# Sheet1.net
KiCad netlist of a schematic drawn in Altium Designer
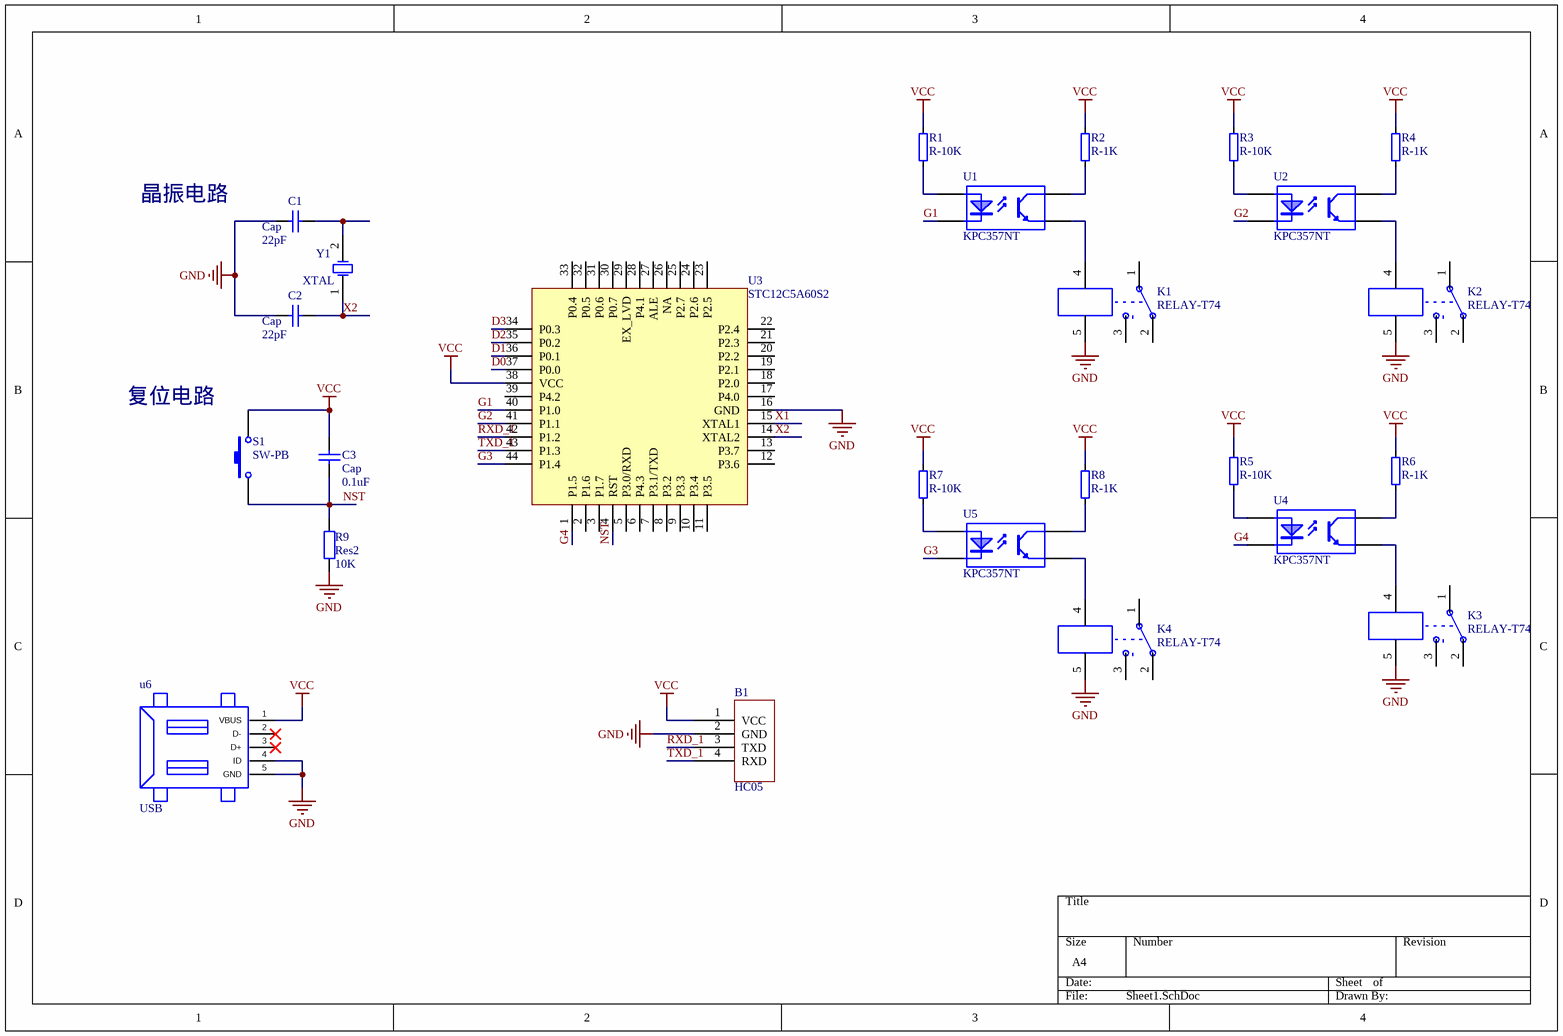
[diagram p0: Sheet1.SchDoc]

(export (version "E")
  (design (tool "Eeschema 10.0.6"))
  (components
    (comp (ref "B1") (value "HC05") (libsource (lib "mine") (part "BT06")))
    (comp (ref "C1")
      (value "Cap")
      (footprint "RAD-0.3")
      (description "Capacitor")
      (fields (field (name "ALTIUM_VALUE") "22pF") (field (name "PUBLISHER") "Altium Limited"))
      (libsource (lib "Miscellaneous Devices") (part "Cap"))
    )
    (comp (ref "C2")
      (value "Cap")
      (footprint "RAD-0.3")
      (description "Capacitor")
      (fields (field (name "ALTIUM_VALUE") "22pF") (field (name "PUBLISHER") "Altium Limited"))
      (libsource (lib "Miscellaneous Devices") (part "Cap"))
    )
    (comp (ref "C3")
      (value "Cap")
      (footprint "RAD-0.3")
      (description "Capacitor")
      (fields (field (name "ALTIUM_VALUE") "0.1uF") (field (name "PUBLISHER") "Altium Limited"))
      (libsource (lib "Miscellaneous Devices") (part "Cap"))
    )
    (comp (ref "K1")
      (value "RELAY-T74")
      (footprint "RELAY-T74")
      (description "CN-RELAY-T74")
      (libsource (lib "常用器件") (part "RELAY-T74"))
    )
    (comp (ref "K2")
      (value "RELAY-T74")
      (footprint "RELAY-T74")
      (description "CN-RELAY-T74")
      (libsource (lib "常用器件") (part "RELAY-T74"))
    )
    (comp (ref "K3")
      (value "RELAY-T74")
      (footprint "RELAY-T74")
      (description "CN-RELAY-T74")
      (libsource (lib "常用器件") (part "RELAY-T74"))
    )
    (comp (ref "K4")
      (value "RELAY-T74")
      (footprint "RELAY-T74")
      (description "CN-RELAY-T74")
      (libsource (lib "常用器件") (part "RELAY-T74"))
    )
    (comp (ref "R1")
      (value "R-10K")
      (footprint "0805R")
      (description "resistor")
      (libsource (lib "常用器件") (part "R-10K"))
    )
    (comp (ref "R2")
      (value "R-1K")
      (footprint "0805R")
      (description "resistor")
      (libsource (lib "常用器件") (part "R-10K"))
    )
    (comp (ref "R3")
      (value "R-10K")
      (footprint "0805R")
      (description "resistor")
      (libsource (lib "常用器件") (part "R-10K"))
    )
    (comp (ref "R4")
      (value "R-1K")
      (footprint "0805R")
      (description "resistor")
      (libsource (lib "常用器件") (part "R-10K"))
    )
    (comp (ref "R5")
      (value "R-10K")
      (footprint "0805R")
      (description "resistor")
      (libsource (lib "常用器件") (part "R-10K"))
    )
    (comp (ref "R6")
      (value "R-1K")
      (footprint "0805R")
      (description "resistor")
      (libsource (lib "常用器件") (part "R-10K"))
    )
    (comp (ref "R7")
      (value "R-10K")
      (footprint "0805R")
      (description "resistor")
      (libsource (lib "常用器件") (part "R-10K"))
    )
    (comp (ref "R8")
      (value "R-1K")
      (footprint "0805R")
      (description "resistor")
      (libsource (lib "常用器件") (part "R-10K"))
    )
    (comp (ref "R9")
      (value "Res2")
      (footprint "AXIAL-0.4")
      (description "Resistor")
      (fields (field (name "ALTIUM_VALUE") "10K") (field (name "PUBLISHER") "Altium Limited"))
      (libsource (lib "Miscellaneous Devices") (part "Res2"))
    )
    (comp (ref "S1")
      (value "SW-PB")
      (footprint "SPST-2")
      (description "Switch")
      (fields (field (name "PUBLISHER") "Altium Limited"))
      (libsource (lib "Miscellaneous Devices") (part "SW-PB"))
    )
    (comp (ref "U1")
      (value "KPC357NT")
      (footprint "DIP-4")
      (fields (field (name "PUBLISHER") "Altium Limited"))
      (libsource (lib "常用器件") (part "KPC357NT"))
    )
    (comp (ref "U2")
      (value "KPC357NT")
      (footprint "DIP-4")
      (fields (field (name "PUBLISHER") "Altium Limited"))
      (libsource (lib "常用器件") (part "KPC357NT"))
    )
    (comp (ref "U3")
      (value "STC12C5A60S2")
      (footprint "TQFP-44")
      (libsource (lib "STC12C5A60") (part "STC12C5A60S2"))
    )
    (comp (ref "U4")
      (value "KPC357NT")
      (footprint "DIP-4")
      (fields (field (name "PUBLISHER") "Altium Limited"))
      (libsource (lib "常用器件") (part "KPC357NT"))
    )
    (comp (ref "U5")
      (value "KPC357NT")
      (footprint "DIP-4")
      (fields (field (name "PUBLISHER") "Altium Limited"))
      (libsource (lib "常用器件") (part "KPC357NT"))
    )
    (comp (ref "u6") (value "USB") (libsource (lib "mine") (part "USB")))
    (comp (ref "Y1")
      (value "XTAL")
      (footprint "R38")
      (description "Crystal Oscillator")
      (fields (field (name "PUBLISHER") "Altium Limited"))
      (libsource (lib "Miscellaneous Devices") (part "XTAL"))
    )
  )
  (nets
    (net (code "1") (name "/D0") (class "Default")
      (node (ref "U3") (pin "37") (pinfunction "P0.0_37") (pintype "passive"))
    )
    (net (code "2") (name "/D1") (class "Default")
      (node (ref "U3") (pin "36") (pinfunction "P0.1_36") (pintype "passive"))
    )
    (net (code "3") (name "/D2") (class "Default")
      (node (ref "U3") (pin "35") (pinfunction "P0.2_35") (pintype "passive"))
    )
    (net (code "4") (name "/D3") (class "Default")
      (node (ref "U3") (pin "34") (pinfunction "P0.3_34") (pintype "passive"))
    )
    (net (code "5") (name "/G1") (class "Default")
      (node (ref "U1") (pin "2") (pinfunction "K_2") (pintype "passive"))
      (node (ref "U3") (pin "40") (pinfunction "P1.0_40") (pintype "passive"))
    )
    (net (code "6") (name "/G2") (class "Default")
      (node (ref "U2") (pin "2") (pinfunction "K_2") (pintype "passive"))
      (node (ref "U3") (pin "41") (pinfunction "P1.1_41") (pintype "passive"))
    )
    (net (code "7") (name "/G3") (class "Default")
      (node (ref "U3") (pin "44") (pinfunction "P1.4_44") (pintype "passive"))
      (node (ref "U5") (pin "2") (pinfunction "K_2") (pintype "passive"))
    )
    (net (code "8") (name "/G4") (class "Default")
      (node (ref "U3") (pin "1") (pinfunction "P1.5_1") (pintype "passive"))
      (node (ref "U4") (pin "2") (pinfunction "K_2") (pintype "passive"))
    )
    (net (code "9") (name "/NST") (class "Default")
      (node (ref "C3") (pin "1") (pinfunction "1_1") (pintype "passive"))
      (node (ref "R9") (pin "2") (pinfunction "2_2") (pintype "passive"))
      (node (ref "S1") (pin "1") (pinfunction "1_1") (pintype "passive"))
      (node (ref "U3") (pin "4") (pinfunction "RST_4") (pintype "passive"))
    )
    (net (code "10") (name "/RXD_1") (class "Default")
      (node (ref "B1") (pin "3") (pinfunction "TXD_3") (pintype "passive"))
      (node (ref "U3") (pin "42") (pinfunction "P1.2_42") (pintype "passive"))
    )
    (net (code "11") (name "/TXD_1") (class "Default")
      (node (ref "B1") (pin "4") (pinfunction "RXD_4") (pintype "passive"))
      (node (ref "U3") (pin "43") (pinfunction "P1.3_43") (pintype "passive"))
    )
    (net (code "12") (name "/X1") (class "Default")
      (node (ref "U3") (pin "15") (pinfunction "XTAL1_15") (pintype "passive"))
    )
    (net (code "13") (name "/X2") (class "Default")
      (node (ref "C2") (pin "2") (pinfunction "2_2") (pintype "passive"))
      (node (ref "U3") (pin "14") (pinfunction "XTAL2_14") (pintype "passive"))
      (node (ref "Y1") (pin "1") (pinfunction "OSC1_1") (pintype "passive"))
    )
    (net (code "14") (name "GND") (class "Default")
      (node (ref "B1") (pin "2") (pinfunction "GND_2") (pintype "passive"))
      (node (ref "C1") (pin "1") (pinfunction "1_1") (pintype "passive"))
      (node (ref "C2") (pin "1") (pinfunction "1_1") (pintype "passive"))
      (node (ref "K1") (pin "5") (pinfunction "5_5") (pintype "passive"))
      (node (ref "K2") (pin "5") (pinfunction "5_5") (pintype "passive"))
      (node (ref "K3") (pin "5") (pinfunction "5_5") (pintype "passive"))
      (node (ref "K4") (pin "5") (pinfunction "5_5") (pintype "passive"))
      (node (ref "R9") (pin "1") (pinfunction "1_1") (pintype "passive"))
      (node (ref "U3") (pin "16") (pinfunction "GND_16") (pintype "power_in"))
      (node (ref "u6") (pin "4") (pinfunction "ID_4") (pintype "passive"))
      (node (ref "u6") (pin "5") (pinfunction "GND_5") (pintype "passive"))
    )
    (net (code "15") (name "Net-(U1-A)") (class "Default")
      (node (ref "R1") (pin "1") (pinfunction "1_1") (pintype "passive"))
      (node (ref "U1") (pin "1") (pinfunction "A_1") (pintype "passive"))
    )
    (net (code "16") (name "Net-(U1-C)") (class "Default")
      (node (ref "R2") (pin "1") (pinfunction "1_1") (pintype "passive"))
      (node (ref "U1") (pin "4") (pinfunction "C_4") (pintype "passive"))
    )
    (net (code "17") (name "Net-(U1-E)") (class "Default")
      (node (ref "K1") (pin "4") (pinfunction "4_4") (pintype "passive"))
      (node (ref "U1") (pin "3") (pinfunction "E_3") (pintype "passive"))
    )
    (net (code "18") (name "Net-(U2-A)") (class "Default")
      (node (ref "R3") (pin "1") (pinfunction "1_1") (pintype "passive"))
      (node (ref "U2") (pin "1") (pinfunction "A_1") (pintype "passive"))
    )
    (net (code "19") (name "Net-(U2-C)") (class "Default")
      (node (ref "R4") (pin "1") (pinfunction "1_1") (pintype "passive"))
      (node (ref "U2") (pin "4") (pinfunction "C_4") (pintype "passive"))
    )
    (net (code "20") (name "Net-(U2-E)") (class "Default")
      (node (ref "K2") (pin "4") (pinfunction "4_4") (pintype "passive"))
      (node (ref "U2") (pin "3") (pinfunction "E_3") (pintype "passive"))
    )
    (net (code "21") (name "Net-(U4-A)") (class "Default")
      (node (ref "R5") (pin "1") (pinfunction "1_1") (pintype "passive"))
      (node (ref "U4") (pin "1") (pinfunction "A_1") (pintype "passive"))
    )
    (net (code "22") (name "Net-(U4-C)") (class "Default")
      (node (ref "R6") (pin "1") (pinfunction "1_1") (pintype "passive"))
      (node (ref "U4") (pin "4") (pinfunction "C_4") (pintype "passive"))
    )
    (net (code "23") (name "Net-(U4-E)") (class "Default")
      (node (ref "K3") (pin "4") (pinfunction "4_4") (pintype "passive"))
      (node (ref "U4") (pin "3") (pinfunction "E_3") (pintype "passive"))
    )
    (net (code "24") (name "Net-(U5-A)") (class "Default")
      (node (ref "R7") (pin "1") (pinfunction "1_1") (pintype "passive"))
      (node (ref "U5") (pin "1") (pinfunction "A_1") (pintype "passive"))
    )
    (net (code "25") (name "Net-(U5-C)") (class "Default")
      (node (ref "R8") (pin "1") (pinfunction "1_1") (pintype "passive"))
      (node (ref "U5") (pin "4") (pinfunction "C_4") (pintype "passive"))
    )
    (net (code "26") (name "Net-(U5-E)") (class "Default")
      (node (ref "K4") (pin "4") (pinfunction "4_4") (pintype "passive"))
      (node (ref "U5") (pin "3") (pinfunction "E_3") (pintype "passive"))
    )
    (net (code "27") (name "Net-(Y1-OSC2)") (class "Default")
      (node (ref "C1") (pin "2") (pinfunction "2_2") (pintype "passive"))
      (node (ref "Y1") (pin "2") (pinfunction "OSC2_2") (pintype "passive"))
    )
    (net (code "28") (name "VCC") (class "Default")
      (node (ref "B1") (pin "1") (pinfunction "VCC_1") (pintype "passive"))
      (node (ref "C3") (pin "2") (pinfunction "2_2") (pintype "passive"))
      (node (ref "R1") (pin "2") (pinfunction "2_2") (pintype "passive"))
      (node (ref "R2") (pin "2") (pinfunction "2_2") (pintype "passive"))
      (node (ref "R3") (pin "2") (pinfunction "2_2") (pintype "passive"))
      (node (ref "R4") (pin "2") (pinfunction "2_2") (pintype "passive"))
      (node (ref "R5") (pin "2") (pinfunction "2_2") (pintype "passive"))
      (node (ref "R6") (pin "2") (pinfunction "2_2") (pintype "passive"))
      (node (ref "R7") (pin "2") (pinfunction "2_2") (pintype "passive"))
      (node (ref "R8") (pin "2") (pinfunction "2_2") (pintype "passive"))
      (node (ref "S1") (pin "2") (pinfunction "2_2") (pintype "passive"))
      (node (ref "U3") (pin "38") (pinfunction "VCC_38") (pintype "power_in"))
      (node (ref "u6") (pin "1") (pinfunction "VBUS_1") (pintype "passive"))
    )
    (net (code "29") (name "unconnected-(K1-Pad1)") (class "Default")
      (node (ref "K1") (pin "1") (pinfunction "1_1") (pintype "passive"))
    )
    (net (code "30") (name "unconnected-(K1-Pad2)") (class "Default")
      (node (ref "K1") (pin "2") (pinfunction "2_2") (pintype "passive"))
    )
    (net (code "31") (name "unconnected-(K1-Pad3)") (class "Default")
      (node (ref "K1") (pin "3") (pinfunction "3_3") (pintype "passive"))
    )
    (net (code "32") (name "unconnected-(K2-Pad1)") (class "Default")
      (node (ref "K2") (pin "1") (pinfunction "1_1") (pintype "passive"))
    )
    (net (code "33") (name "unconnected-(K2-Pad2)") (class "Default")
      (node (ref "K2") (pin "2") (pinfunction "2_2") (pintype "passive"))
    )
    (net (code "34") (name "unconnected-(K2-Pad3)") (class "Default")
      (node (ref "K2") (pin "3") (pinfunction "3_3") (pintype "passive"))
    )
    (net (code "35") (name "unconnected-(K3-Pad1)") (class "Default")
      (node (ref "K3") (pin "1") (pinfunction "1_1") (pintype "passive"))
    )
    (net (code "36") (name "unconnected-(K3-Pad2)") (class "Default")
      (node (ref "K3") (pin "2") (pinfunction "2_2") (pintype "passive"))
    )
    (net (code "37") (name "unconnected-(K3-Pad3)") (class "Default")
      (node (ref "K3") (pin "3") (pinfunction "3_3") (pintype "passive"))
    )
    (net (code "38") (name "unconnected-(K4-Pad1)") (class "Default")
      (node (ref "K4") (pin "1") (pinfunction "1_1") (pintype "passive"))
    )
    (net (code "39") (name "unconnected-(K4-Pad2)") (class "Default")
      (node (ref "K4") (pin "2") (pinfunction "2_2") (pintype "passive"))
    )
    (net (code "40") (name "unconnected-(K4-Pad3)") (class "Default")
      (node (ref "K4") (pin "3") (pinfunction "3_3") (pintype "passive"))
    )
    (net (code "41") (name "unconnected-(U3-ALE-Pad27)") (class "Default")
      (node (ref "U3") (pin "27") (pinfunction "ALE_27") (pintype "passive"))
    )
    (net (code "42") (name "unconnected-(U3-EX_LVD-Pad29)") (class "Default")
      (node (ref "U3") (pin "29") (pinfunction "EX_LVD_29") (pintype "passive"))
    )
    (net (code "43") (name "unconnected-(U3-NA-Pad26)") (class "Default")
      (node (ref "U3") (pin "26") (pinfunction "NA_26") (pintype "passive"))
    )
    (net (code "44") (name "unconnected-(U3-P0.4-Pad33)") (class "Default")
      (node (ref "U3") (pin "33") (pinfunction "P0.4_33") (pintype "passive"))
    )
    (net (code "45") (name "unconnected-(U3-P0.5-Pad32)") (class "Default")
      (node (ref "U3") (pin "32") (pinfunction "P0.5_32") (pintype "passive"))
    )
    (net (code "46") (name "unconnected-(U3-P0.6-Pad31)") (class "Default")
      (node (ref "U3") (pin "31") (pinfunction "P0.6_31") (pintype "passive"))
    )
    (net (code "47") (name "unconnected-(U3-P0.7-Pad30)") (class "Default")
      (node (ref "U3") (pin "30") (pinfunction "P0.7_30") (pintype "passive"))
    )
    (net (code "48") (name "unconnected-(U3-P1.6-Pad2)") (class "Default")
      (node (ref "U3") (pin "2") (pinfunction "P1.6_2") (pintype "passive"))
    )
    (net (code "49") (name "unconnected-(U3-P1.7-Pad3)") (class "Default")
      (node (ref "U3") (pin "3") (pinfunction "P1.7_3") (pintype "passive"))
    )
    (net (code "50") (name "unconnected-(U3-P2.0-Pad18)") (class "Default")
      (node (ref "U3") (pin "18") (pinfunction "P2.0_18") (pintype "passive"))
    )
    (net (code "51") (name "unconnected-(U3-P2.1-Pad19)") (class "Default")
      (node (ref "U3") (pin "19") (pinfunction "P2.1_19") (pintype "passive"))
    )
    (net (code "52") (name "unconnected-(U3-P2.2-Pad20)") (class "Default")
      (node (ref "U3") (pin "20") (pinfunction "P2.2_20") (pintype "passive"))
    )
    (net (code "53") (name "unconnected-(U3-P2.3-Pad21)") (class "Default")
      (node (ref "U3") (pin "21") (pinfunction "P2.3_21") (pintype "passive"))
    )
    (net (code "54") (name "unconnected-(U3-P2.4-Pad22)") (class "Default")
      (node (ref "U3") (pin "22") (pinfunction "P2.4_22") (pintype "passive"))
    )
    (net (code "55") (name "unconnected-(U3-P2.5-Pad23)") (class "Default")
      (node (ref "U3") (pin "23") (pinfunction "P2.5_23") (pintype "passive"))
    )
    (net (code "56") (name "unconnected-(U3-P2.6-Pad24)") (class "Default")
      (node (ref "U3") (pin "24") (pinfunction "P2.6_24") (pintype "passive"))
    )
    (net (code "57") (name "unconnected-(U3-P2.7-Pad25)") (class "Default")
      (node (ref "U3") (pin "25") (pinfunction "P2.7_25") (pintype "passive"))
    )
    (net (code "58") (name "unconnected-(U3-P3.0{slash}RXD-Pad5)") (class "Default")
      (node (ref "U3") (pin "5") (pinfunction "P3.0/RXD_5") (pintype "passive"))
    )
    (net (code "59") (name "unconnected-(U3-P3.1{slash}TXD-Pad7)") (class "Default")
      (node (ref "U3") (pin "7") (pinfunction "P3.1/TXD_7") (pintype "passive"))
    )
    (net (code "60") (name "unconnected-(U3-P3.2-Pad8)") (class "Default")
      (node (ref "U3") (pin "8") (pinfunction "P3.2_8") (pintype "passive"))
    )
    (net (code "61") (name "unconnected-(U3-P3.3-Pad9)") (class "Default")
      (node (ref "U3") (pin "9") (pinfunction "P3.3_9") (pintype "passive"))
    )
    (net (code "62") (name "unconnected-(U3-P3.4-Pad10)") (class "Default")
      (node (ref "U3") (pin "10") (pinfunction "P3.4_10") (pintype "passive"))
    )
    (net (code "63") (name "unconnected-(U3-P3.5-Pad11)") (class "Default")
      (node (ref "U3") (pin "11") (pinfunction "P3.5_11") (pintype "passive"))
    )
    (net (code "64") (name "unconnected-(U3-P3.6-Pad12)") (class "Default")
      (node (ref "U3") (pin "12") (pinfunction "P3.6_12") (pintype "passive"))
    )
    (net (code "65") (name "unconnected-(U3-P3.7-Pad13)") (class "Default")
      (node (ref "U3") (pin "13") (pinfunction "P3.7_13") (pintype "passive"))
    )
    (net (code "66") (name "unconnected-(U3-P4.0-Pad17)") (class "Default")
      (node (ref "U3") (pin "17") (pinfunction "P4.0_17") (pintype "passive"))
    )
    (net (code "67") (name "unconnected-(U3-P4.1-Pad28)") (class "Default")
      (node (ref "U3") (pin "28") (pinfunction "P4.1_28") (pintype "passive"))
    )
    (net (code "68") (name "unconnected-(U3-P4.2-Pad39)") (class "Default")
      (node (ref "U3") (pin "39") (pinfunction "P4.2_39") (pintype "passive"))
    )
    (net (code "69") (name "unconnected-(U3-P4.3-Pad6)") (class "Default")
      (node (ref "U3") (pin "6") (pinfunction "P4.3_6") (pintype "passive"))
    )
    (net (code "70") (name "unconnected-(u6-D+-Pad3)") (class "Default")
      (node (ref "u6") (pin "3") (pinfunction "D+_3") (pintype "passive+no_connect"))
    )
    (net (code "71") (name "unconnected-(u6-D--Pad2)") (class "Default")
      (node (ref "u6") (pin "2") (pinfunction "D-_2") (pintype "passive+no_connect"))
    )
  )
)
